# LED_PWM.net
KiCad netlist of a schematic drawn in EAGLE
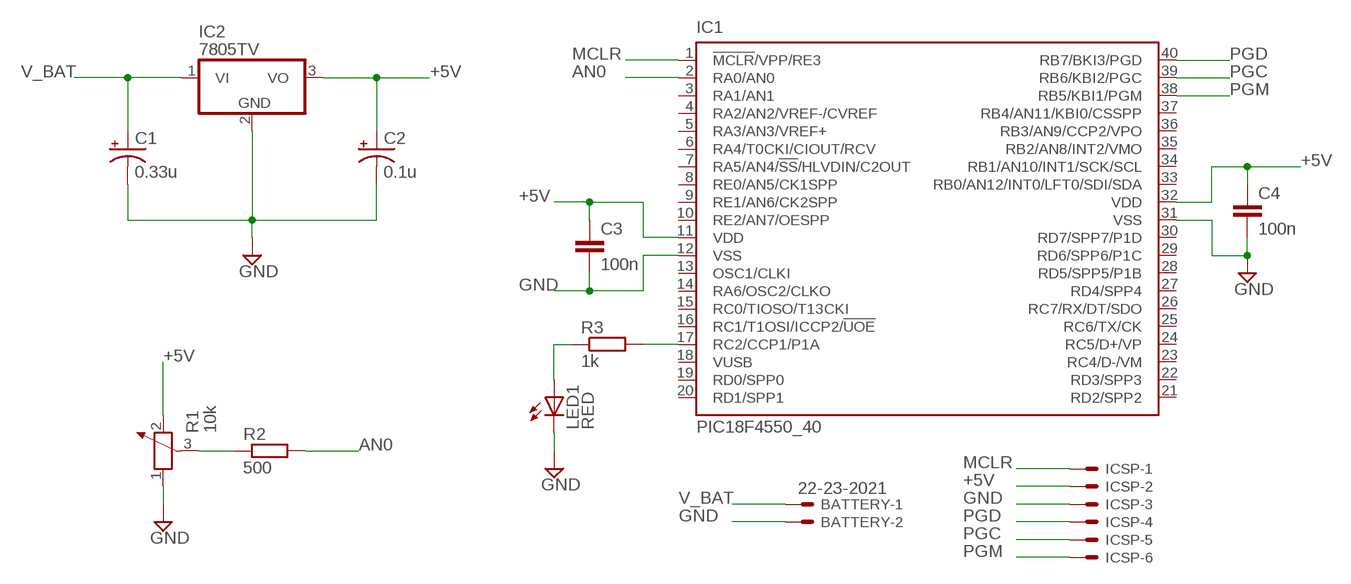
[diagram p0: schematic, sheet 1]

(export (version "E")
  (design (tool "Eeschema 10.0.6"))
  (components
    (comp (ref "BATTERY")
      (value "22-23-2021")
      (footprint "eagle-import:22-23-2021")
      (fields (field (name "MF") "MOLEX"))
      (libsource (lib "eagle-import") (part "22-23-2021"))
    )
    (comp (ref "C1")
      (value "0.33u")
      (footprint "eagle-import:E1,8-4")
      (libsource (lib "eagle-import") (part "CPOL-USE1.8-4"))
    )
    (comp (ref "C2")
      (value "0.1u")
      (footprint "eagle-import:E1,8-4")
      (libsource (lib "eagle-import") (part "CPOL-USE1.8-4"))
    )
    (comp (ref "C3")
      (value "100n")
      (footprint "eagle-import:C025-024X044")
      (libsource (lib "eagle-import") (part "C-EU025-024X044"))
    )
    (comp (ref "C4")
      (value "100n")
      (footprint "eagle-import:C025-024X044")
      (libsource (lib "eagle-import") (part "C-EU025-024X044"))
    )
    (comp (ref "IC1")
      (value "PIC18F4550_40")
      (footprint "eagle-import:DIL40")
      (fields (field (name "MF") "MICROCHIP") (field (name "MPN") "PIC18F4550-I/P"))
      (libsource (lib "eagle-import") (part "PIC18F4_40550"))
    )
    (comp (ref "IC2")
      (value "7805TV")
      (footprint "eagle-import:TO220V")
      (libsource (lib "eagle-import") (part "78TV05"))
    )
    (comp (ref "ICSP")
      (value "22-23-2061")
      (footprint "eagle-import:22-23-2061")
      (fields (field (name "MF") "MOLEX"))
      (libsource (lib "eagle-import") (part "22-23-2061"))
    )
    (comp (ref "LED1")
      (value "RED")
      (footprint "eagle-import:LED3MM")
      (libsource (lib "eagle-import") (part "LED3MM"))
    )
    (comp (ref "R1")
      (value "10k")
      (footprint "eagle-import:PT-10")
      (libsource (lib "eagle-import") (part "POTENTIOMETER_PT-10"))
    )
    (comp (ref "R2")
      (value "500")
      (footprint "eagle-import:0204_5")
      (libsource (lib "eagle-import") (part "R-EU_0204/5"))
    )
    (comp (ref "R3")
      (value "1k")
      (footprint "eagle-import:0204_5")
      (libsource (lib "eagle-import") (part "R-EU_0204/5"))
    )
  )
  (nets
    (net (code "1") (name "/+5V") (class "Default")
      (node (ref "C2") (pin "+") (pinfunction "+_+") (pintype "passive"))
      (node (ref "C3") (pin "1") (pinfunction "1_1") (pintype "passive"))
      (node (ref "C4") (pin "1") (pinfunction "1_1") (pintype "passive"))
      (node (ref "IC1") (pin "11") (pinfunction "VDD_11") (pintype "power_in"))
      (node (ref "IC1") (pin "32") (pinfunction "VDD_32") (pintype "power_in"))
      (node (ref "IC2") (pin "3") (pinfunction "VO_3") (pintype "passive"))
      (node (ref "ICSP") (pin "2") (pinfunction "S_2") (pintype "passive"))
      (node (ref "R1") (pin "2") (pinfunction "2_2") (pintype "passive"))
    )
    (net (code "2") (name "/AN0") (class "Default")
      (node (ref "IC1") (pin "2") (pinfunction "RA0/AN0_2") (pintype "bidirectional"))
      (node (ref "R2") (pin "2") (pinfunction "2_2") (pintype "passive"))
    )
    (net (code "3") (name "/MCLR") (class "Default")
      (node (ref "IC1") (pin "1") (pinfunction "~{MCLR}/VPP/RE3_1") (pintype "input"))
      (node (ref "ICSP") (pin "1") (pinfunction "S_1") (pintype "passive"))
    )
    (net (code "4") (name "/PGC") (class "Default")
      (node (ref "IC1") (pin "39") (pinfunction "RB6/KBI2/PGC_39") (pintype "bidirectional"))
      (node (ref "ICSP") (pin "5") (pinfunction "S_5") (pintype "passive"))
    )
    (net (code "5") (name "/PGD") (class "Default")
      (node (ref "IC1") (pin "40") (pinfunction "RB7/BKI3/PGD_40") (pintype "bidirectional"))
      (node (ref "ICSP") (pin "4") (pinfunction "S_4") (pintype "passive"))
    )
    (net (code "6") (name "/PGM") (class "Default")
      (node (ref "IC1") (pin "38") (pinfunction "RB5/KBI1/PGM_38") (pintype "bidirectional"))
      (node (ref "ICSP") (pin "6") (pinfunction "S_6") (pintype "passive"))
    )
    (net (code "7") (name "/V_BAT") (class "Default")
      (node (ref "BATTERY") (pin "1") (pinfunction "S_1") (pintype "passive"))
      (node (ref "C1") (pin "+") (pinfunction "+_+") (pintype "passive"))
      (node (ref "IC2") (pin "1") (pinfunction "VI_1") (pintype "input"))
    )
    (net (code "8") (name "GND") (class "Default")
      (node (ref "BATTERY") (pin "2") (pinfunction "S_2") (pintype "passive"))
      (node (ref "C1") (pin "-") (pinfunction "-_-") (pintype "passive"))
      (node (ref "C2") (pin "-") (pinfunction "-_-") (pintype "passive"))
      (node (ref "C3") (pin "2") (pinfunction "2_2") (pintype "passive"))
      (node (ref "C4") (pin "2") (pinfunction "2_2") (pintype "passive"))
      (node (ref "IC1") (pin "12") (pinfunction "VSS_12") (pintype "power_in"))
      (node (ref "IC1") (pin "31") (pinfunction "VSS_31") (pintype "power_in"))
      (node (ref "IC2") (pin "2") (pinfunction "GND_2") (pintype "passive"))
      (node (ref "ICSP") (pin "3") (pinfunction "S_3") (pintype "passive"))
      (node (ref "LED1") (pin "K") (pinfunction "C_K") (pintype "passive"))
      (node (ref "R1") (pin "1") (pinfunction "1_1") (pintype "passive"))
    )
    (net (code "9") (name "Net-(IC1-RC2{slash}CCP1{slash}P1A)") (class "Default")
      (node (ref "IC1") (pin "17") (pinfunction "RC2/CCP1/P1A_17") (pintype "bidirectional"))
      (node (ref "R3") (pin "2") (pinfunction "2_2") (pintype "passive"))
    )
    (net (code "10") (name "Net-(LED1-PadA)") (class "Default")
      (node (ref "LED1") (pin "A") (pinfunction "A_A") (pintype "passive"))
      (node (ref "R3") (pin "1") (pinfunction "1_1") (pintype "passive"))
    )
    (net (code "11") (name "Net-(R1-Pad3)") (class "Default")
      (node (ref "R1") (pin "3") (pinfunction "3_3") (pintype "passive"))
      (node (ref "R2") (pin "1") (pinfunction "1_1") (pintype "passive"))
    )
    (net (code "12") (name "unconnected-(IC1-OSC1{slash}CLKI-Pad13)") (class "Default")
      (node (ref "IC1") (pin "13") (pinfunction "OSC1/CLKI_13") (pintype "input"))
    )
    (net (code "13") (name "unconnected-(IC1-RA1{slash}AN1-Pad3)") (class "Default")
      (node (ref "IC1") (pin "3") (pinfunction "RA1/AN1_3") (pintype "bidirectional"))
    )
    (net (code "14") (name "unconnected-(IC1-RA2{slash}AN2{slash}VREF-{slash}CVREF-Pad4)") (class "Default")
      (node (ref "IC1") (pin "4") (pinfunction "RA2/AN2/VREF-/CVREF_4") (pintype "bidirectional"))
    )
    (net (code "15") (name "unconnected-(IC1-RA3{slash}AN3{slash}VREF+-Pad5)") (class "Default")
      (node (ref "IC1") (pin "5") (pinfunction "RA3/AN3/VREF+_5") (pintype "bidirectional"))
    )
    (net (code "16") (name "unconnected-(IC1-RA4{slash}T0CKI{slash}CIOUT{slash}RCV-Pad6)") (class "Default")
      (node (ref "IC1") (pin "6") (pinfunction "RA4/T0CKI/CIOUT/RCV_6") (pintype "bidirectional"))
    )
    (net (code "17") (name "unconnected-(IC1-RA5{slash}AN4{slash}~{SS}{slash}HLVDIN{slash}C2OUT-Pad7)") (class "Default")
      (node (ref "IC1") (pin "7") (pinfunction "RA5/AN4/~{SS}/HLVDIN/C2OUT_7") (pintype "bidirectional"))
    )
    (net (code "18") (name "unconnected-(IC1-RA6{slash}OSC2{slash}CLKO-Pad14)") (class "Default")
      (node (ref "IC1") (pin "14") (pinfunction "RA6/OSC2/CLKO_14") (pintype "output"))
    )
    (net (code "19") (name "unconnected-(IC1-RB0{slash}AN12{slash}INT0{slash}LFT0{slash}SDI{slash}SDA-Pad33)") (class "Default")
      (node (ref "IC1") (pin "33") (pinfunction "RB0/AN12/INT0/LFT0/SDI/SDA_33") (pintype "bidirectional"))
    )
    (net (code "20") (name "unconnected-(IC1-RB1{slash}AN10{slash}INT1{slash}SCK{slash}SCL-Pad34)") (class "Default")
      (node (ref "IC1") (pin "34") (pinfunction "RB1/AN10/INT1/SCK/SCL_34") (pintype "bidirectional"))
    )
    (net (code "21") (name "unconnected-(IC1-RB2{slash}AN8{slash}INT2{slash}VMO-Pad35)") (class "Default")
      (node (ref "IC1") (pin "35") (pinfunction "RB2/AN8/INT2/VMO_35") (pintype "bidirectional"))
    )
    (net (code "22") (name "unconnected-(IC1-RB3{slash}AN9{slash}CCP2{slash}VPO-Pad36)") (class "Default")
      (node (ref "IC1") (pin "36") (pinfunction "RB3/AN9/CCP2/VPO_36") (pintype "bidirectional"))
    )
    (net (code "23") (name "unconnected-(IC1-RB4{slash}AN11{slash}KBI0{slash}CSSPP-Pad37)") (class "Default")
      (node (ref "IC1") (pin "37") (pinfunction "RB4/AN11/KBI0/CSSPP_37") (pintype "bidirectional"))
    )
    (net (code "24") (name "unconnected-(IC1-RC0{slash}TIOSO{slash}T13CKI-Pad15)") (class "Default")
      (node (ref "IC1") (pin "15") (pinfunction "RC0/TIOSO/T13CKI_15") (pintype "bidirectional"))
    )
    (net (code "25") (name "unconnected-(IC1-RC1{slash}T1OSI{slash}ICCP2{slash}~{UOE}-Pad16)") (class "Default")
      (node (ref "IC1") (pin "16") (pinfunction "RC1/T1OSI/ICCP2/~{UOE}_16") (pintype "bidirectional"))
    )
    (net (code "26") (name "unconnected-(IC1-RC4{slash}D-{slash}VM-Pad23)") (class "Default")
      (node (ref "IC1") (pin "23") (pinfunction "RC4/D-/VM_23") (pintype "bidirectional"))
    )
    (net (code "27") (name "unconnected-(IC1-RC5{slash}D+{slash}VP-Pad24)") (class "Default")
      (node (ref "IC1") (pin "24") (pinfunction "RC5/D+/VP_24") (pintype "bidirectional"))
    )
    (net (code "28") (name "unconnected-(IC1-RC6{slash}TX{slash}CK-Pad25)") (class "Default")
      (node (ref "IC1") (pin "25") (pinfunction "RC6/TX/CK_25") (pintype "bidirectional"))
    )
    (net (code "29") (name "unconnected-(IC1-RC7{slash}RX{slash}DT{slash}SDO-Pad26)") (class "Default")
      (node (ref "IC1") (pin "26") (pinfunction "RC7/RX/DT/SDO_26") (pintype "bidirectional"))
    )
    (net (code "30") (name "unconnected-(IC1-RD0{slash}SPP0-Pad19)") (class "Default")
      (node (ref "IC1") (pin "19") (pinfunction "RD0/SPP0_19") (pintype "bidirectional"))
    )
    (net (code "31") (name "unconnected-(IC1-RD1{slash}SPP1-Pad20)") (class "Default")
      (node (ref "IC1") (pin "20") (pinfunction "RD1/SPP1_20") (pintype "bidirectional"))
    )
    (net (code "32") (name "unconnected-(IC1-RD2{slash}SPP2-Pad21)") (class "Default")
      (node (ref "IC1") (pin "21") (pinfunction "RD2/SPP2_21") (pintype "bidirectional"))
    )
    (net (code "33") (name "unconnected-(IC1-RD3{slash}SPP3-Pad22)") (class "Default")
      (node (ref "IC1") (pin "22") (pinfunction "RD3/SPP3_22") (pintype "bidirectional"))
    )
    (net (code "34") (name "unconnected-(IC1-RD4{slash}SPP4-Pad27)") (class "Default")
      (node (ref "IC1") (pin "27") (pinfunction "RD4/SPP4_27") (pintype "bidirectional"))
    )
    (net (code "35") (name "unconnected-(IC1-RD5{slash}SPP5{slash}P1B-Pad28)") (class "Default")
      (node (ref "IC1") (pin "28") (pinfunction "RD5/SPP5/P1B_28") (pintype "bidirectional"))
    )
    (net (code "36") (name "unconnected-(IC1-RD6{slash}SPP6{slash}P1C-Pad29)") (class "Default")
      (node (ref "IC1") (pin "29") (pinfunction "RD6/SPP6/P1C_29") (pintype "bidirectional"))
    )
    (net (code "37") (name "unconnected-(IC1-RD7{slash}SPP7{slash}P1D-Pad30)") (class "Default")
      (node (ref "IC1") (pin "30") (pinfunction "RD7/SPP7/P1D_30") (pintype "bidirectional"))
    )
    (net (code "38") (name "unconnected-(IC1-RE0{slash}AN5{slash}CK1SPP-Pad8)") (class "Default")
      (node (ref "IC1") (pin "8") (pinfunction "RE0/AN5/CK1SPP_8") (pintype "bidirectional"))
    )
    (net (code "39") (name "unconnected-(IC1-RE1{slash}AN6{slash}CK2SPP-Pad9)") (class "Default")
      (node (ref "IC1") (pin "9") (pinfunction "RE1/AN6/CK2SPP_9") (pintype "bidirectional"))
    )
    (net (code "40") (name "unconnected-(IC1-RE2{slash}AN7{slash}OESPP-Pad10)") (class "Default")
      (node (ref "IC1") (pin "10") (pinfunction "RE2/AN7/OESPP_10") (pintype "bidirectional"))
    )
    (net (code "41") (name "unconnected-(IC1-VUSB-Pad18)") (class "Default")
      (node (ref "IC1") (pin "18") (pinfunction "VUSB_18") (pintype "bidirectional"))
    )
  )
)
